# Leak_Detector_v3.net
KiCad netlist of a schematic drawn in EAGLE
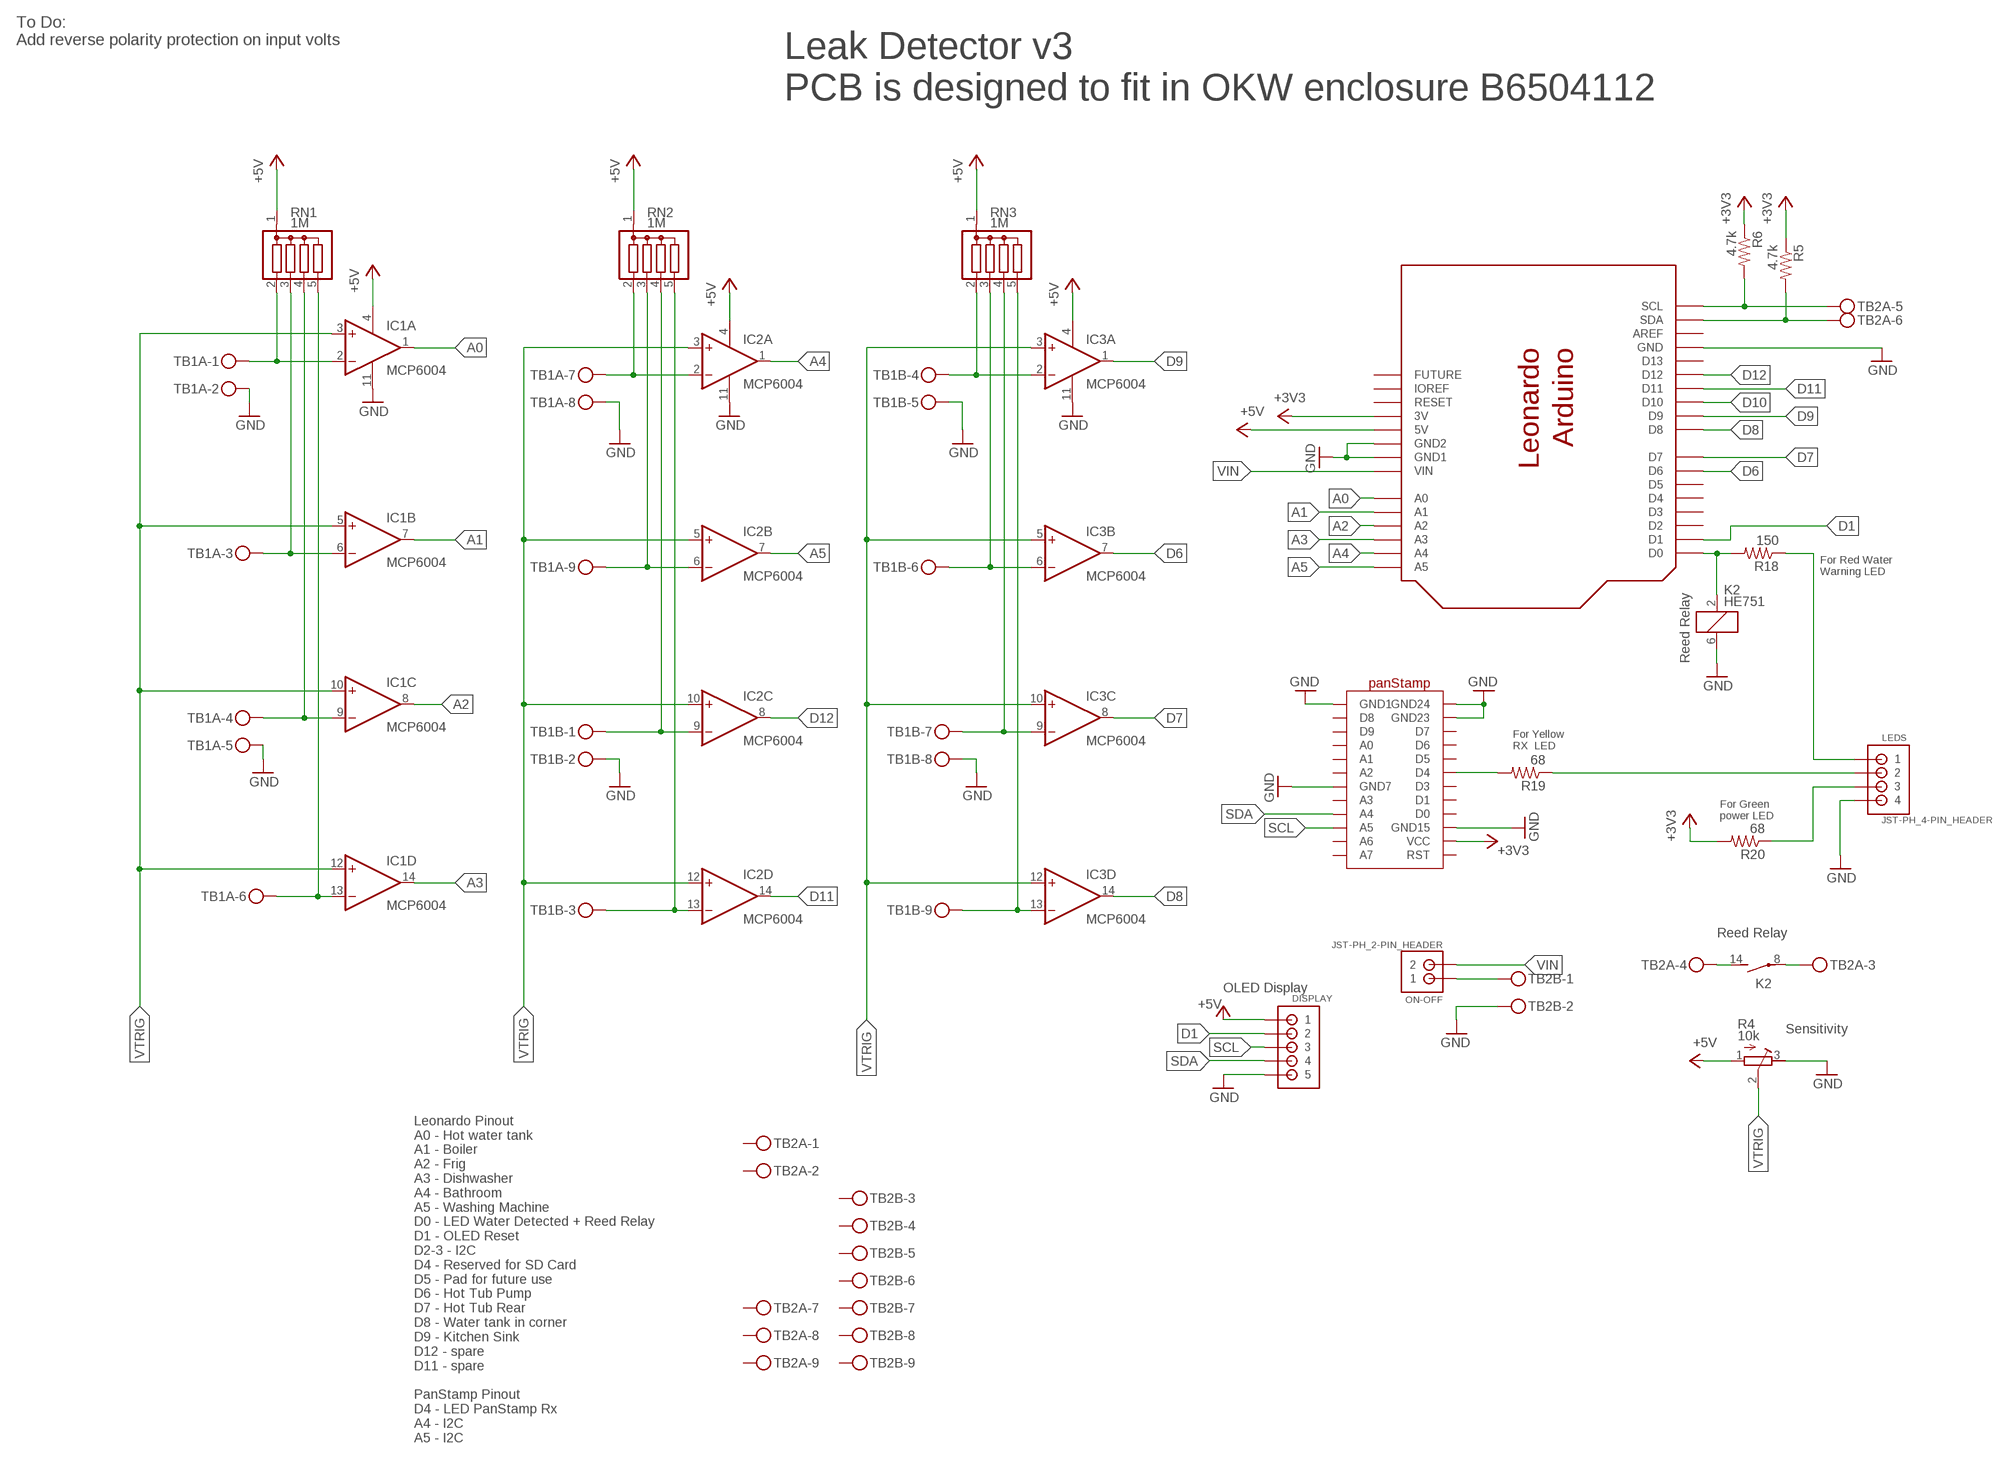
[diagram p0: schematic, sheet 1]

(export (version "E")
  (design (tool "Eeschema 10.0.6"))
  (components
    (comp (ref "DISPLAY")
      (value "JST-PH_5-PIN_HEADER")
      (footprint "eagle-import:JST_B5B-PH_HEADER")
      (libsource (lib "eagle-import") (part "JST-PH_5-PIN_HEADER"))
    )
    (comp (ref "IC1")
      (value "MCP6004")
      (footprint "eagle-import:DIL14")
      (libsource (lib "eagle-import") (part "MCP604P"))
    )
    (comp (ref "IC2")
      (value "MCP6004")
      (footprint "eagle-import:DIL14")
      (libsource (lib "eagle-import") (part "MCP604P"))
    )
    (comp (ref "IC3")
      (value "MCP6004")
      (footprint "eagle-import:DIL14")
      (libsource (lib "eagle-import") (part "MCP604P"))
    )
    (comp (ref "K2")
      (value "HE751")
      (footprint "eagle-import:HE751")
      (libsource (lib "eagle-import") (part "HE751"))
    )
    (comp (ref "LEDS")
      (value "JST-PH_4-PIN_HEADER")
      (footprint "eagle-import:JST_B4B-PH_HEADER")
      (libsource (lib "eagle-import") (part "JST-PH_4-PIN_HEADER"))
    )
    (comp (ref "ON-OFF")
      (value "JST-PH_2-PIN_HEADER")
      (footprint "eagle-import:JST_B2B-PH_HEADER")
      (libsource (lib "eagle-import") (part "JST-PH_2-PIN_HEADER"))
    )
    (comp (ref "R4")
      (value "10k")
      (footprint "eagle-import:RTRIM3296P")
      (libsource (lib "eagle-import") (part "R-TRIMM3296P"))
    )
    (comp (ref "R5")
      (value "4.7k")
      (footprint "eagle-import:0207_10")
      (libsource (lib "eagle-import") (part "R-US_0207/10"))
    )
    (comp (ref "R6")
      (value "4.7k")
      (footprint "eagle-import:0207_10")
      (libsource (lib "eagle-import") (part "R-US_0207/10"))
    )
    (comp (ref "R18")
      (value "150")
      (footprint "eagle-import:0207_10")
      (libsource (lib "eagle-import") (part "R-US_0207/10"))
    )
    (comp (ref "R19")
      (value "68")
      (footprint "eagle-import:0207_10")
      (libsource (lib "eagle-import") (part "R-US_0207/10"))
    )
    (comp (ref "R20")
      (value "68")
      (footprint "eagle-import:0207_10")
      (libsource (lib "eagle-import") (part "R-US_0207/10"))
    )
    (comp (ref "RN1")
      (value "1M")
      (footprint "eagle-import:SIL5")
      (libsource (lib "eagle-import") (part "G04R"))
    )
    (comp (ref "RN2")
      (value "1M")
      (footprint "eagle-import:SIL5")
      (libsource (lib "eagle-import") (part "G04R"))
    )
    (comp (ref "RN3")
      (value "1M")
      (footprint "eagle-import:SIL5")
      (libsource (lib "eagle-import") (part "G04R"))
    )
    (comp (ref "TB1A")
      (value "MKDSN1,5/9-5,08")
      (footprint "eagle-import:MKDSN1,5_9-5,08")
      (fields (field (name "MPN") "SMKDSN1,5/9-5,08"))
      (libsource (lib "eagle-import") (part "MKDSN1,5/9-5,08"))
    )
    (comp (ref "TB1B")
      (value "MKDSN1,5/9-5,08")
      (footprint "eagle-import:MKDSN1,5_9-5,08")
      (fields (field (name "MPN") "SMKDSN1,5/9-5,08"))
      (libsource (lib "eagle-import") (part "MKDSN1,5/9-5,08"))
    )
    (comp (ref "TB2A")
      (value "MKDSN1,5/9-5,08")
      (footprint "eagle-import:MKDSN1,5_9-5,08")
      (fields (field (name "MPN") "SMKDSN1,5/9-5,08"))
      (libsource (lib "eagle-import") (part "MKDSN1,5/9-5,08"))
    )
    (comp (ref "TB2B")
      (value "MKDSN1,5/9-5,08")
      (footprint "eagle-import:MKDSN1,5_9-5,08")
      (fields (field (name "MPN") "SMKDSN1,5/9-5,08"))
      (libsource (lib "eagle-import") (part "MKDSN1,5/9-5,08"))
    )
    (comp (ref "U$1")
      (value "ARDUINO_LEONARDO")
      (footprint "eagle-import:ARDUINO_LEONARDO")
      (libsource (lib "eagle-import") (part "ARDUINO_LEONARDO"))
    )
    (comp (ref "U$2")
      (value "PANSTAMP")
      (footprint "eagle-import:PANSTAMP")
      (libsource (lib "eagle-import") (part "PANSTAMP"))
    )
  )
  (nets
    (net (code "1") (name "+3V3") (class "Default")
      (node (ref "R20") (pin "2") (pinfunction "2_2") (pintype "passive"))
      (node (ref "R5") (pin "1") (pinfunction "1_1") (pintype "passive"))
      (node (ref "R6") (pin "1") (pinfunction "1_1") (pintype "passive"))
      (node (ref "U$1") (pin "3V") (pinfunction "3V_3V") (pintype "power_in"))
      (node (ref "U$2") (pin "VCC") (pinfunction "VCC_VCC") (pintype "power_in"))
    )
    (net (code "2") (name "+5V") (class "Default")
      (node (ref "DISPLAY") (pin "P1") (pinfunction "1_P1") (pintype "bidirectional"))
      (node (ref "IC1") (pin "4") (pinfunction "V+_4") (pintype "power_in"))
      (node (ref "IC2") (pin "4") (pinfunction "V+_4") (pintype "power_in"))
      (node (ref "IC3") (pin "4") (pinfunction "V+_4") (pintype "power_in"))
      (node (ref "R4") (pin "1") (pinfunction "E_1") (pintype "passive"))
      (node (ref "RN1") (pin "1") (pinfunction "1_1") (pintype "passive"))
      (node (ref "RN2") (pin "1") (pinfunction "1_1") (pintype "passive"))
      (node (ref "RN3") (pin "1") (pinfunction "1_1") (pintype "passive"))
      (node (ref "U$1") (pin "5V") (pinfunction "5V_5V") (pintype "power_in"))
    )
    (net (code "3") (name "A0") (class "Default")
      (node (ref "IC1") (pin "1") (pinfunction "OUT_1") (pintype "output"))
      (node (ref "U$1") (pin "A0") (pinfunction "A0_A0") (pintype "bidirectional"))
    )
    (net (code "4") (name "A1") (class "Default")
      (node (ref "IC1") (pin "7") (pinfunction "OUT_7") (pintype "output"))
      (node (ref "U$1") (pin "A1") (pinfunction "A1_A1") (pintype "bidirectional"))
    )
    (net (code "5") (name "A2") (class "Default")
      (node (ref "IC1") (pin "8") (pinfunction "OUT_8") (pintype "output"))
      (node (ref "U$1") (pin "A2") (pinfunction "A2_A2") (pintype "bidirectional"))
    )
    (net (code "6") (name "A3") (class "Default")
      (node (ref "IC1") (pin "14") (pinfunction "OUT_14") (pintype "output"))
      (node (ref "U$1") (pin "A3") (pinfunction "A3_A3") (pintype "bidirectional"))
    )
    (net (code "7") (name "A4") (class "Default")
      (node (ref "IC2") (pin "1") (pinfunction "OUT_1") (pintype "output"))
      (node (ref "U$1") (pin "A4") (pinfunction "A4_A4") (pintype "bidirectional"))
    )
    (net (code "8") (name "A5") (class "Default")
      (node (ref "IC2") (pin "7") (pinfunction "OUT_7") (pintype "output"))
      (node (ref "U$1") (pin "A5") (pinfunction "A5_A5") (pintype "bidirectional"))
    )
    (net (code "9") (name "D1") (class "Default")
      (node (ref "DISPLAY") (pin "P2") (pinfunction "2_P2") (pintype "bidirectional"))
      (node (ref "U$1") (pin "D1") (pinfunction "D1_D1") (pintype "bidirectional"))
    )
    (net (code "10") (name "D6") (class "Default")
      (node (ref "IC3") (pin "7") (pinfunction "OUT_7") (pintype "output"))
      (node (ref "U$1") (pin "D6") (pinfunction "D6_D6") (pintype "bidirectional"))
    )
    (net (code "11") (name "D7") (class "Default")
      (node (ref "IC3") (pin "8") (pinfunction "OUT_8") (pintype "output"))
      (node (ref "U$1") (pin "D7") (pinfunction "D7_D7") (pintype "bidirectional"))
    )
    (net (code "12") (name "D8") (class "Default")
      (node (ref "IC3") (pin "14") (pinfunction "OUT_14") (pintype "output"))
      (node (ref "U$1") (pin "D8") (pinfunction "D8_D8") (pintype "bidirectional"))
    )
    (net (code "13") (name "D9") (class "Default")
      (node (ref "IC3") (pin "1") (pinfunction "OUT_1") (pintype "output"))
      (node (ref "U$1") (pin "D9") (pinfunction "D9_D9") (pintype "bidirectional"))
    )
    (net (code "14") (name "D10") (class "Default")
      (node (ref "U$1") (pin "D10") (pinfunction "D10_D10") (pintype "bidirectional"))
    )
    (net (code "15") (name "D11") (class "Default")
      (node (ref "IC2") (pin "14") (pinfunction "OUT_14") (pintype "output"))
      (node (ref "U$1") (pin "D11") (pinfunction "D11_D11") (pintype "bidirectional"))
    )
    (net (code "16") (name "D12") (class "Default")
      (node (ref "IC2") (pin "8") (pinfunction "OUT_8") (pintype "output"))
      (node (ref "U$1") (pin "D12") (pinfunction "D12_D12") (pintype "bidirectional"))
    )
    (net (code "17") (name "GND") (class "Default")
      (node (ref "DISPLAY") (pin "P5") (pinfunction "5_P5") (pintype "bidirectional"))
      (node (ref "IC1") (pin "11") (pinfunction "V-_11") (pintype "power_in"))
      (node (ref "IC2") (pin "11") (pinfunction "V-_11") (pintype "power_in"))
      (node (ref "IC3") (pin "11") (pinfunction "V-_11") (pintype "power_in"))
      (node (ref "K2") (pin "6") (pinfunction "2_6") (pintype "passive"))
      (node (ref "LEDS") (pin "P4") (pinfunction "4_P4") (pintype "bidirectional"))
      (node (ref "R4") (pin "3") (pinfunction "A_3") (pintype "passive"))
      (node (ref "TB1A") (pin "2") (pinfunction "KL_2") (pintype "passive"))
      (node (ref "TB1A") (pin "5") (pinfunction "KL_5") (pintype "passive"))
      (node (ref "TB1A") (pin "8") (pinfunction "KL_8") (pintype "passive"))
      (node (ref "TB1B") (pin "2") (pinfunction "KL_2") (pintype "passive"))
      (node (ref "TB1B") (pin "5") (pinfunction "KL_5") (pintype "passive"))
      (node (ref "TB1B") (pin "8") (pinfunction "KL_8") (pintype "passive"))
      (node (ref "TB2B") (pin "2") (pinfunction "KL_2") (pintype "passive"))
      (node (ref "U$1") (pin "GND") (pinfunction "GND_GND") (pintype "power_in"))
      (node (ref "U$1") (pin "GND$2") (pinfunction "GND2_GND$2") (pintype "power_in"))
      (node (ref "U$1") (pin "GND$3") (pinfunction "GND1_GND$3") (pintype "power_in"))
      (node (ref "U$2") (pin "GND1") (pinfunction "GND1_GND1") (pintype "power_in"))
      (node (ref "U$2") (pin "GND15") (pinfunction "GND15_GND15") (pintype "power_in"))
      (node (ref "U$2") (pin "GND23") (pinfunction "GND23_GND23") (pintype "power_in"))
      (node (ref "U$2") (pin "GND24") (pinfunction "GND24_GND24") (pintype "power_in"))
      (node (ref "U$2") (pin "GND7") (pinfunction "GND7_GND7") (pintype "power_in"))
    )
    (net (code "18") (name "Net-(IC1A--IN)") (class "Default")
      (node (ref "IC1") (pin "2") (pinfunction "-IN_2") (pintype "input"))
      (node (ref "RN1") (pin "2") (pinfunction "2_2") (pintype "passive"))
      (node (ref "TB1A") (pin "1") (pinfunction "KL_1") (pintype "passive"))
    )
    (net (code "19") (name "Net-(IC1B--IN)") (class "Default")
      (node (ref "IC1") (pin "6") (pinfunction "-IN_6") (pintype "input"))
      (node (ref "RN1") (pin "3") (pinfunction "3_3") (pintype "passive"))
      (node (ref "TB1A") (pin "3") (pinfunction "KL_3") (pintype "passive"))
    )
    (net (code "20") (name "Net-(IC1C--IN)") (class "Default")
      (node (ref "IC1") (pin "9") (pinfunction "-IN_9") (pintype "input"))
      (node (ref "RN1") (pin "4") (pinfunction "4_4") (pintype "passive"))
      (node (ref "TB1A") (pin "4") (pinfunction "KL_4") (pintype "passive"))
    )
    (net (code "21") (name "Net-(IC1D--IN)") (class "Default")
      (node (ref "IC1") (pin "13") (pinfunction "-IN_13") (pintype "input"))
      (node (ref "RN1") (pin "5") (pinfunction "5_5") (pintype "passive"))
      (node (ref "TB1A") (pin "6") (pinfunction "KL_6") (pintype "passive"))
    )
    (net (code "22") (name "Net-(IC2A--IN)") (class "Default")
      (node (ref "IC2") (pin "2") (pinfunction "-IN_2") (pintype "input"))
      (node (ref "RN2") (pin "2") (pinfunction "2_2") (pintype "passive"))
      (node (ref "TB1A") (pin "7") (pinfunction "KL_7") (pintype "passive"))
    )
    (net (code "23") (name "Net-(IC2B--IN)") (class "Default")
      (node (ref "IC2") (pin "6") (pinfunction "-IN_6") (pintype "input"))
      (node (ref "RN2") (pin "3") (pinfunction "3_3") (pintype "passive"))
      (node (ref "TB1A") (pin "9") (pinfunction "KL_9") (pintype "passive"))
    )
    (net (code "24") (name "Net-(IC2C--IN)") (class "Default")
      (node (ref "IC2") (pin "9") (pinfunction "-IN_9") (pintype "input"))
      (node (ref "RN2") (pin "4") (pinfunction "4_4") (pintype "passive"))
      (node (ref "TB1B") (pin "1") (pinfunction "KL_1") (pintype "passive"))
    )
    (net (code "25") (name "Net-(IC2D--IN)") (class "Default")
      (node (ref "IC2") (pin "13") (pinfunction "-IN_13") (pintype "input"))
      (node (ref "RN2") (pin "5") (pinfunction "5_5") (pintype "passive"))
      (node (ref "TB1B") (pin "3") (pinfunction "KL_3") (pintype "passive"))
    )
    (net (code "26") (name "Net-(IC3A--IN)") (class "Default")
      (node (ref "IC3") (pin "2") (pinfunction "-IN_2") (pintype "input"))
      (node (ref "RN3") (pin "2") (pinfunction "2_2") (pintype "passive"))
      (node (ref "TB1B") (pin "4") (pinfunction "KL_4") (pintype "passive"))
    )
    (net (code "27") (name "Net-(IC3B--IN)") (class "Default")
      (node (ref "IC3") (pin "6") (pinfunction "-IN_6") (pintype "input"))
      (node (ref "RN3") (pin "3") (pinfunction "3_3") (pintype "passive"))
      (node (ref "TB1B") (pin "6") (pinfunction "KL_6") (pintype "passive"))
    )
    (net (code "28") (name "Net-(IC3C--IN)") (class "Default")
      (node (ref "IC3") (pin "9") (pinfunction "-IN_9") (pintype "input"))
      (node (ref "RN3") (pin "4") (pinfunction "4_4") (pintype "passive"))
      (node (ref "TB1B") (pin "7") (pinfunction "KL_7") (pintype "passive"))
    )
    (net (code "29") (name "Net-(IC3D--IN)") (class "Default")
      (node (ref "IC3") (pin "13") (pinfunction "-IN_13") (pintype "input"))
      (node (ref "RN3") (pin "5") (pinfunction "5_5") (pintype "passive"))
      (node (ref "TB1B") (pin "9") (pinfunction "KL_9") (pintype "passive"))
    )
    (net (code "30") (name "Net-(K2A-1)") (class "Default")
      (node (ref "K2") (pin "2") (pinfunction "1_2") (pintype "passive"))
      (node (ref "R18") (pin "2") (pinfunction "2_2") (pintype "passive"))
      (node (ref "U$1") (pin "D0") (pinfunction "D0_D0") (pintype "bidirectional"))
    )
    (net (code "31") (name "Net-(K2B-P)") (class "Default")
      (node (ref "K2") (pin "8") (pinfunction "P_8") (pintype "passive"))
      (node (ref "TB2A") (pin "3") (pinfunction "KL_3") (pintype "passive"))
    )
    (net (code "32") (name "Net-(K2B-S)") (class "Default")
      (node (ref "K2") (pin "14") (pinfunction "S_14") (pintype "passive"))
      (node (ref "TB2A") (pin "4") (pinfunction "KL_4") (pintype "passive"))
    )
    (net (code "33") (name "Net-(LEDS-1)") (class "Default")
      (node (ref "LEDS") (pin "P1") (pinfunction "1_P1") (pintype "bidirectional"))
      (node (ref "R18") (pin "1") (pinfunction "1_1") (pintype "passive"))
    )
    (net (code "34") (name "Net-(LEDS-2)") (class "Default")
      (node (ref "LEDS") (pin "P2") (pinfunction "2_P2") (pintype "bidirectional"))
      (node (ref "R19") (pin "1") (pinfunction "1_1") (pintype "passive"))
    )
    (net (code "35") (name "Net-(LEDS-3)") (class "Default")
      (node (ref "LEDS") (pin "P3") (pinfunction "3_P3") (pintype "bidirectional"))
      (node (ref "R20") (pin "1") (pinfunction "1_1") (pintype "passive"))
    )
    (net (code "36") (name "Net-(ON-OFF-1)") (class "Default")
      (node (ref "ON-OFF") (pin "P1") (pinfunction "1_P1") (pintype "bidirectional"))
      (node (ref "TB2B") (pin "1") (pinfunction "KL_1") (pintype "passive"))
    )
    (net (code "37") (name "Net-(R19-Pad2)") (class "Default")
      (node (ref "R19") (pin "2") (pinfunction "2_2") (pintype "passive"))
      (node (ref "U$2") (pin "D4") (pinfunction "D4_D4") (pintype "bidirectional"))
    )
    (net (code "38") (name "SCL") (class "Default")
      (node (ref "DISPLAY") (pin "P3") (pinfunction "3_P3") (pintype "bidirectional"))
      (node (ref "R6") (pin "2") (pinfunction "2_2") (pintype "passive"))
      (node (ref "TB2A") (pin "5") (pinfunction "KL_5") (pintype "passive"))
      (node (ref "U$1") (pin "SCL") (pinfunction "SCL_SCL") (pintype "bidirectional"))
      (node (ref "U$2") (pin "A5") (pinfunction "A5_A5") (pintype "bidirectional"))
    )
    (net (code "39") (name "SDA") (class "Default")
      (node (ref "DISPLAY") (pin "P4") (pinfunction "4_P4") (pintype "bidirectional"))
      (node (ref "R5") (pin "2") (pinfunction "2_2") (pintype "passive"))
      (node (ref "TB2A") (pin "6") (pinfunction "KL_6") (pintype "passive"))
      (node (ref "U$1") (pin "SDA") (pinfunction "SDA_SDA") (pintype "bidirectional"))
      (node (ref "U$2") (pin "A4") (pinfunction "A4_A4") (pintype "bidirectional"))
    )
    (net (code "40") (name "VIN") (class "Default")
      (node (ref "ON-OFF") (pin "P2") (pinfunction "2_P2") (pintype "bidirectional"))
      (node (ref "U$1") (pin "VIN") (pinfunction "VIN_VIN") (pintype "power_in"))
    )
    (net (code "41") (name "VTRIG") (class "Default")
      (node (ref "IC1") (pin "10") (pinfunction "+IN_10") (pintype "input"))
      (node (ref "IC1") (pin "12") (pinfunction "+IN_12") (pintype "input"))
      (node (ref "IC1") (pin "3") (pinfunction "+IN_3") (pintype "input"))
      (node (ref "IC1") (pin "5") (pinfunction "+IN_5") (pintype "input"))
      (node (ref "IC2") (pin "10") (pinfunction "+IN_10") (pintype "input"))
      (node (ref "IC2") (pin "12") (pinfunction "+IN_12") (pintype "input"))
      (node (ref "IC2") (pin "3") (pinfunction "+IN_3") (pintype "input"))
      (node (ref "IC2") (pin "5") (pinfunction "+IN_5") (pintype "input"))
      (node (ref "IC3") (pin "10") (pinfunction "+IN_10") (pintype "input"))
      (node (ref "IC3") (pin "12") (pinfunction "+IN_12") (pintype "input"))
      (node (ref "IC3") (pin "3") (pinfunction "+IN_3") (pintype "input"))
      (node (ref "IC3") (pin "5") (pinfunction "+IN_5") (pintype "input"))
      (node (ref "R4") (pin "2") (pinfunction "S_2") (pintype "passive"))
    )
    (net (code "42") (name "unconnected-(TB2AA-KL-Pad1)") (class "Default")
      (node (ref "TB2A") (pin "1") (pinfunction "KL_1") (pintype "passive"))
    )
    (net (code "43") (name "unconnected-(TB2AB-KL-Pad2)") (class "Default")
      (node (ref "TB2A") (pin "2") (pinfunction "KL_2") (pintype "passive"))
    )
    (net (code "44") (name "unconnected-(TB2AG-KL-Pad7)") (class "Default")
      (node (ref "TB2A") (pin "7") (pinfunction "KL_7") (pintype "passive"))
    )
    (net (code "45") (name "unconnected-(TB2AH-KL-Pad8)") (class "Default")
      (node (ref "TB2A") (pin "8") (pinfunction "KL_8") (pintype "passive"))
    )
    (net (code "46") (name "unconnected-(TB2AI-KL-Pad9)") (class "Default")
      (node (ref "TB2A") (pin "9") (pinfunction "KL_9") (pintype "passive"))
    )
    (net (code "47") (name "unconnected-(TB2BC-KL-Pad3)") (class "Default")
      (node (ref "TB2B") (pin "3") (pinfunction "KL_3") (pintype "passive"))
    )
    (net (code "48") (name "unconnected-(TB2BD-KL-Pad4)") (class "Default")
      (node (ref "TB2B") (pin "4") (pinfunction "KL_4") (pintype "passive"))
    )
    (net (code "49") (name "unconnected-(TB2BE-KL-Pad5)") (class "Default")
      (node (ref "TB2B") (pin "5") (pinfunction "KL_5") (pintype "passive"))
    )
    (net (code "50") (name "unconnected-(TB2BF-KL-Pad6)") (class "Default")
      (node (ref "TB2B") (pin "6") (pinfunction "KL_6") (pintype "passive"))
    )
    (net (code "51") (name "unconnected-(TB2BG-KL-Pad7)") (class "Default")
      (node (ref "TB2B") (pin "7") (pinfunction "KL_7") (pintype "passive"))
    )
    (net (code "52") (name "unconnected-(TB2BH-KL-Pad8)") (class "Default")
      (node (ref "TB2B") (pin "8") (pinfunction "KL_8") (pintype "passive"))
    )
    (net (code "53") (name "unconnected-(TB2BI-KL-Pad9)") (class "Default")
      (node (ref "TB2B") (pin "9") (pinfunction "KL_9") (pintype "passive"))
    )
    (net (code "54") (name "unconnected-(U$1-FUTURE-PadRESERVED)") (class "Default")
      (node (ref "U$1") (pin "RESERVED") (pinfunction "FUTURE_RESERVED") (pintype "bidirectional"))
    )
    (net (code "55") (name "unconnected-(U$1-PadAREF)") (class "Default")
      (node (ref "U$1") (pin "AREF") (pinfunction "AREF_AREF") (pintype "bidirectional"))
    )
    (net (code "56") (name "unconnected-(U$1-PadD2)") (class "Default")
      (node (ref "U$1") (pin "D2") (pinfunction "D2_D2") (pintype "bidirectional"))
    )
    (net (code "57") (name "unconnected-(U$1-PadD3)") (class "Default")
      (node (ref "U$1") (pin "D3") (pinfunction "D3_D3") (pintype "bidirectional"))
    )
    (net (code "58") (name "unconnected-(U$1-PadD4)") (class "Default")
      (node (ref "U$1") (pin "D4") (pinfunction "D4_D4") (pintype "bidirectional"))
    )
    (net (code "59") (name "unconnected-(U$1-PadD5)") (class "Default")
      (node (ref "U$1") (pin "D5") (pinfunction "D5_D5") (pintype "bidirectional"))
    )
    (net (code "60") (name "unconnected-(U$1-PadD13)") (class "Default")
      (node (ref "U$1") (pin "D13") (pinfunction "D13_D13") (pintype "bidirectional"))
    )
    (net (code "61") (name "unconnected-(U$1-PadIOREF)") (class "Default")
      (node (ref "U$1") (pin "IOREF") (pinfunction "IOREF_IOREF") (pintype "bidirectional"))
    )
    (net (code "62") (name "unconnected-(U$1-PadRESET)") (class "Default")
      (node (ref "U$1") (pin "RESET") (pinfunction "RESET_RESET") (pintype "bidirectional"))
    )
    (net (code "63") (name "unconnected-(U$2-PadA0)") (class "Default")
      (node (ref "U$2") (pin "A0") (pinfunction "A0_A0") (pintype "bidirectional"))
    )
    (net (code "64") (name "unconnected-(U$2-PadA1)") (class "Default")
      (node (ref "U$2") (pin "A1") (pinfunction "A1_A1") (pintype "bidirectional"))
    )
    (net (code "65") (name "unconnected-(U$2-PadA2)") (class "Default")
      (node (ref "U$2") (pin "A2") (pinfunction "A2_A2") (pintype "bidirectional"))
    )
    (net (code "66") (name "unconnected-(U$2-PadA3)") (class "Default")
      (node (ref "U$2") (pin "A3") (pinfunction "A3_A3") (pintype "bidirectional"))
    )
    (net (code "67") (name "unconnected-(U$2-PadA6)") (class "Default")
      (node (ref "U$2") (pin "A6") (pinfunction "A6_A6") (pintype "bidirectional"))
    )
    (net (code "68") (name "unconnected-(U$2-PadA7)") (class "Default")
      (node (ref "U$2") (pin "A7") (pinfunction "A7_A7") (pintype "bidirectional"))
    )
    (net (code "69") (name "unconnected-(U$2-PadD0)") (class "Default")
      (node (ref "U$2") (pin "D0") (pinfunction "D0_D0") (pintype "bidirectional"))
    )
    (net (code "70") (name "unconnected-(U$2-PadD1)") (class "Default")
      (node (ref "U$2") (pin "D1") (pinfunction "D1_D1") (pintype "bidirectional"))
    )
    (net (code "71") (name "unconnected-(U$2-PadD3)") (class "Default")
      (node (ref "U$2") (pin "D3") (pinfunction "D3_D3") (pintype "bidirectional"))
    )
    (net (code "72") (name "unconnected-(U$2-PadD5)") (class "Default")
      (node (ref "U$2") (pin "D5") (pinfunction "D5_D5") (pintype "bidirectional"))
    )
    (net (code "73") (name "unconnected-(U$2-PadD6)") (class "Default")
      (node (ref "U$2") (pin "D6") (pinfunction "D6_D6") (pintype "bidirectional"))
    )
    (net (code "74") (name "unconnected-(U$2-PadD7)") (class "Default")
      (node (ref "U$2") (pin "D7") (pinfunction "D7_D7") (pintype "bidirectional"))
    )
    (net (code "75") (name "unconnected-(U$2-PadD8)") (class "Default")
      (node (ref "U$2") (pin "D8") (pinfunction "D8_D8") (pintype "bidirectional"))
    )
    (net (code "76") (name "unconnected-(U$2-PadD9)") (class "Default")
      (node (ref "U$2") (pin "D9") (pinfunction "D9_D9") (pintype "bidirectional"))
    )
    (net (code "77") (name "unconnected-(U$2-RST-PadRESET)") (class "Default")
      (node (ref "U$2") (pin "RESET") (pinfunction "RST_RESET") (pintype "bidirectional"))
    )
  )
)
